# LED_Driver_-_1.net
KiCad netlist of a schematic drawn in Altium Designer
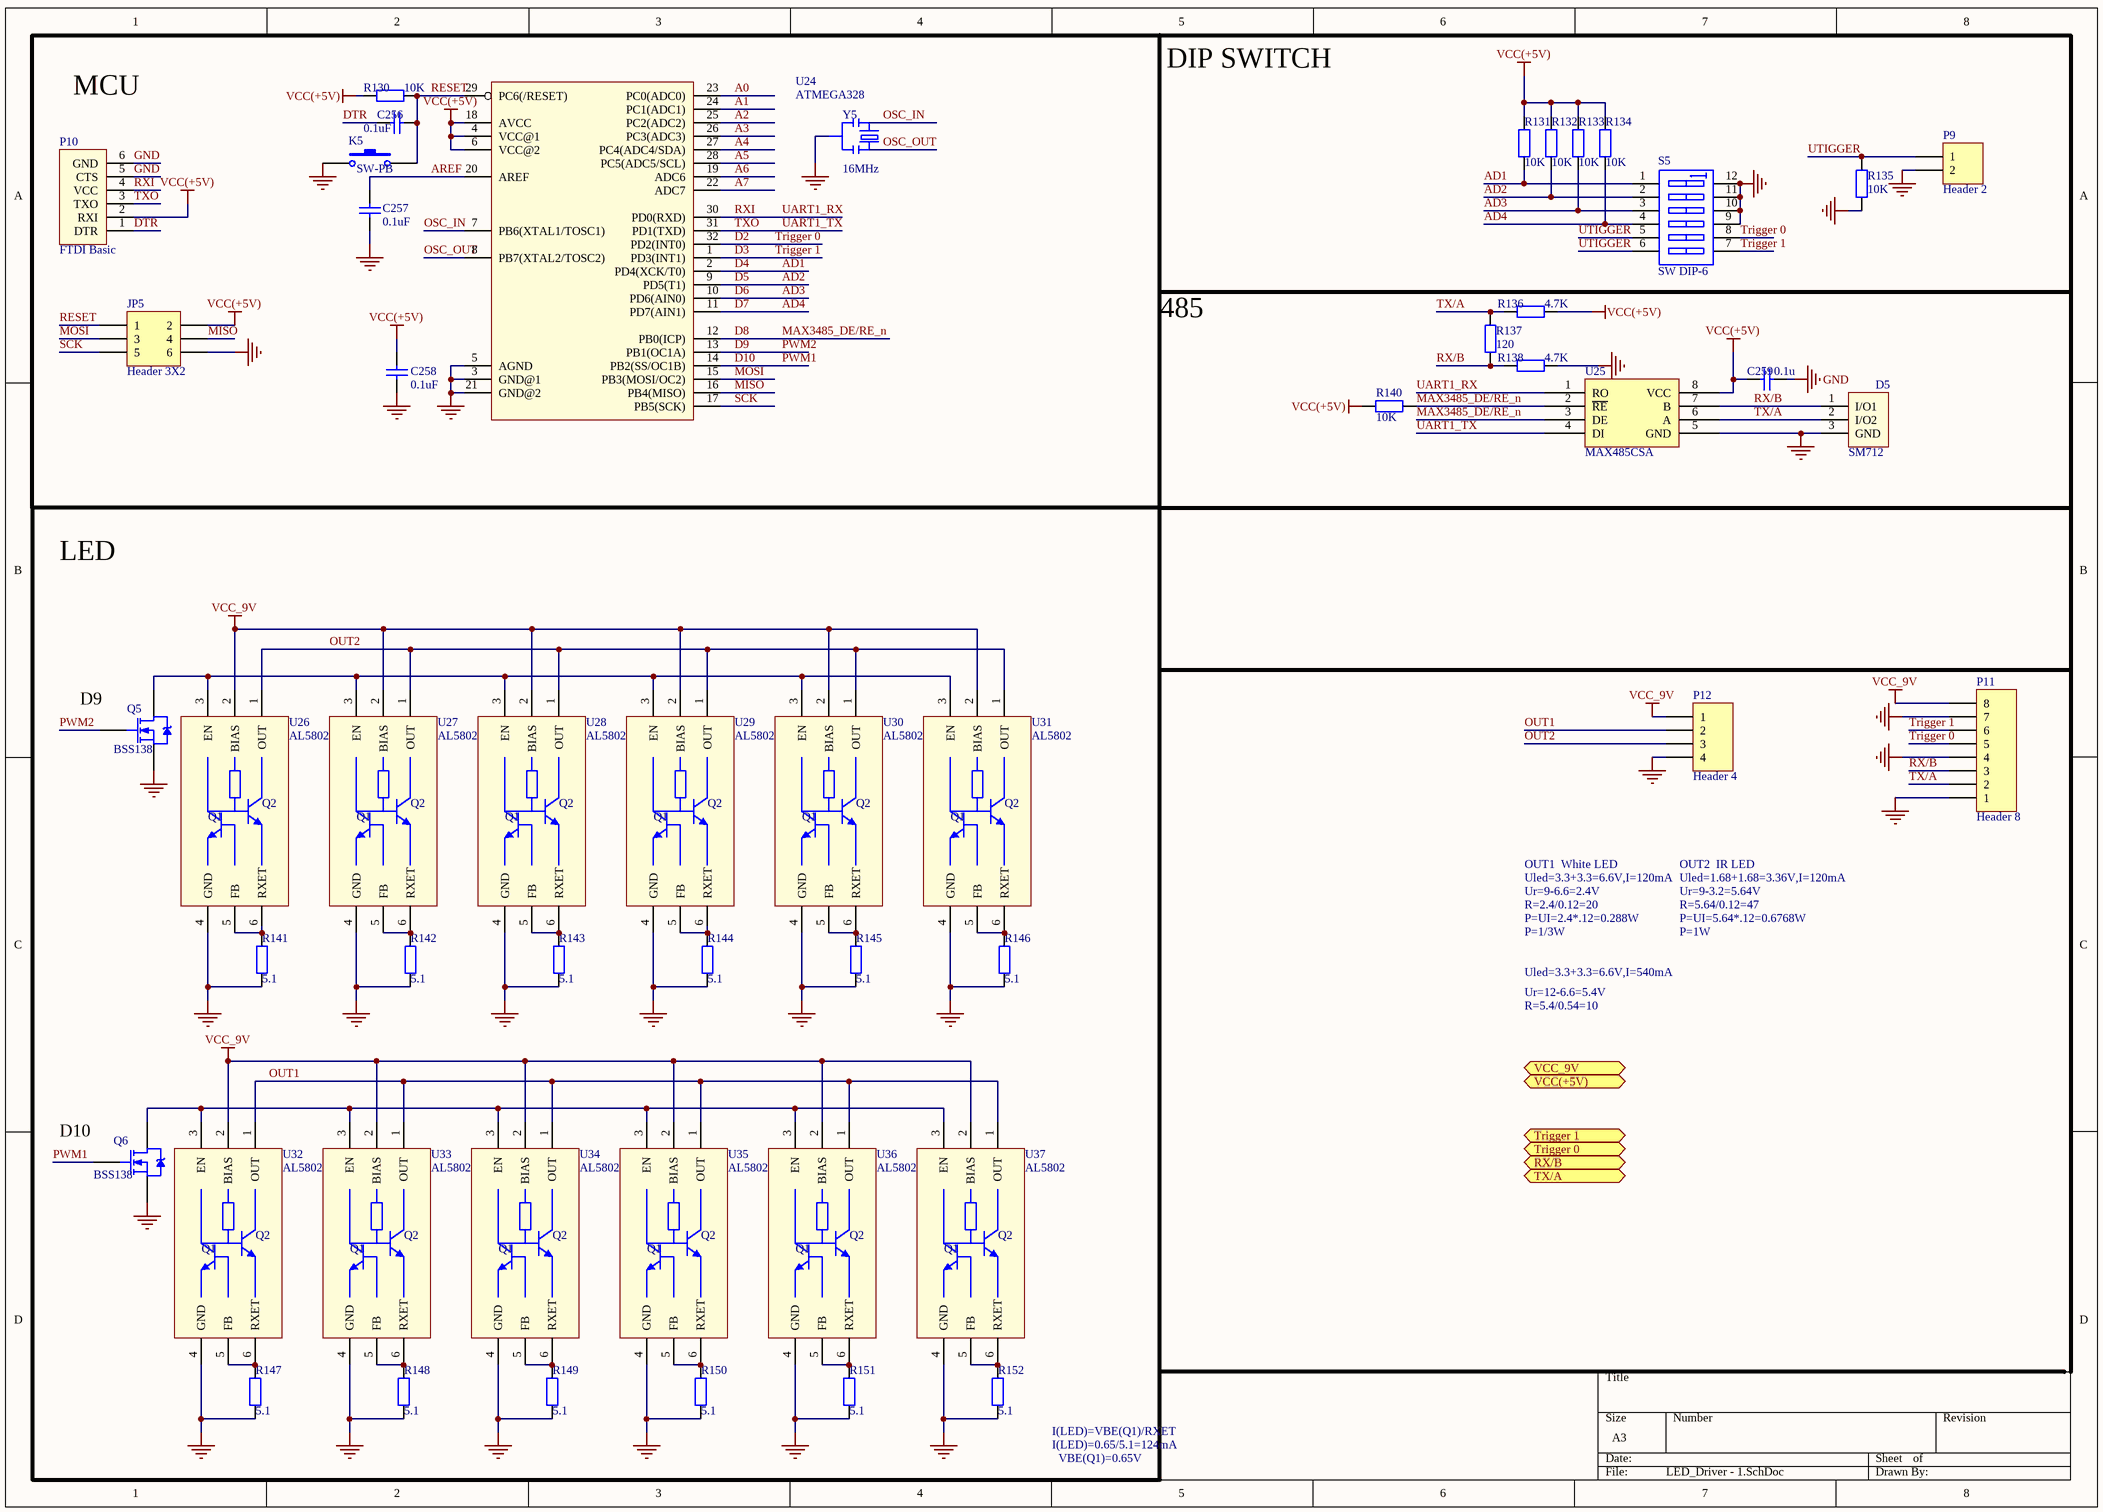
[diagram p0: LED_Driver - 1.SchDoc]

(export (version "E")
  (design (tool "Eeschema 10.0.6"))
  (components
    (comp (ref "C256")
      (value "0.1uF")
      (footprint "C0603")
      (description "Capacitor")
      (fields (field (name "IPARTNUMBER") "C100nF25V10%X7R") (field (name "VOLTAGE") "25V"))
      (libsource (lib "Schlib1") (part "CAP SMT C100nF25V10%X7R"))
    )
    (comp (ref "C257")
      (value "0.1uF")
      (footprint "C0603")
      (description "Capacitor")
      (fields (field (name "IPARTNUMBER") "C100nF25V10%X7R") (field (name "VOLTAGE") "25V"))
      (libsource (lib "Schlib1") (part "CAP SMT C100nF25V10%X7R"))
    )
    (comp (ref "C258")
      (value "0.1uF")
      (footprint "C0603")
      (description "Capacitor")
      (fields (field (name "IPARTNUMBER") "C100nF25V10%X7R") (field (name "VOLTAGE") "25V"))
      (libsource (lib "Schlib1") (part "CAP SMT C100nF25V10%X7R"))
    )
    (comp (ref "C259")
      (value "0.1u")
      (footprint "C0603")
      (description "Capacitor")
      (fields (field (name "PUBLISHER") "Altium Limited"))
      (libsource (lib "Miscellaneous Devices") (part "Cap"))
    )
    (comp (ref "D5")
      (value "SM712")
      (footprint "SOT23-3")
      (libsource (lib "STM32F4_CAM V2.0") (part "SM712"))
    )
    (comp (ref "JP5")
      (value "Header 3X2")
      (footprint "MHDR1X6")
      (description "Header, 3-Pin, Dual row")
      (fields (field (name "PUBLISHER") "Altium Limited"))
      (libsource (lib "Miscellaneous Connectors") (part "Header 3X2"))
    )
    (comp (ref "K5")
      (value "SW-PB")
      (footprint "157SW")
      (description "Switch")
      (fields (field (name "PUBLISHER") "Altium Limited"))
      (libsource (lib "Miscellaneous Devices") (part "SW-PB"))
    )
    (comp (ref "P9")
      (value "Header 2")
      (footprint "HDR1X2")
      (description "Header, 2-Pin")
      (fields (field (name "PUBLISHER") "Altium Limited"))
      (libsource (lib "Miscellaneous Connectors") (part "Header 2"))
    )
    (comp (ref "P10")
      (value "FTDI Basic")
      (footprint "MHDR1X6")
      (libsource (lib "PCB_Project1") (part "ARDUINO_SERIAL_PROGRAMPTH"))
    )
    (comp (ref "P11")
      (value "Header 8")
      (footprint "SH_1.25MM*8")
      (description "Header, 8-Pin")
      (fields (field (name "PUBLISHER") "Altium Limited"))
      (libsource (lib "Miscellaneous Connectors") (part "Header 8"))
    )
    (comp (ref "P12")
      (value "Header 4")
      (footprint "SMT_1.25MM*4")
      (description "Header, 4-Pin")
      (fields (field (name "PUBLISHER") "Altium Limited"))
      (libsource (lib "Miscellaneous Connectors") (part "Header 4"))
    )
    (comp (ref "Q5")
      (value "BSS138")
      (footprint "SOT-23 (Standard)")
      (fields
        (field (name "MANUFACTURER") "Fairchild Semiconductor")
        (field (name "MANUFACTURER PART NUMBER") "BSS123")
      )
      (libsource (lib "Miscellaneous_Devices") (part "NMOS"))
    )
    (comp (ref "Q6")
      (value "BSS138")
      (footprint "SOT-23 (Standard)")
      (fields
        (field (name "MANUFACTURER") "Fairchild Semiconductor")
        (field (name "MANUFACTURER PART NUMBER") "BSS123")
      )
      (libsource (lib "Miscellaneous_Devices") (part "NMOS"))
    )
    (comp (ref "R130")
      (value "10K")
      (footprint "R0603")
      (description "Resistor")
      (libsource (lib "") (part "Res2_2"))
    )
    (comp (ref "R131")
      (value "10K")
      (footprint "R0603")
      (description "Resistor")
      (libsource (lib "DM642") (part "Res2"))
    )
    (comp (ref "R132")
      (value "10K")
      (footprint "R0603")
      (description "Resistor")
      (libsource (lib "DM642") (part "Res2"))
    )
    (comp (ref "R133")
      (value "10K")
      (footprint "R0603")
      (description "Resistor")
      (libsource (lib "DM642") (part "Res2"))
    )
    (comp (ref "R134")
      (value "10K")
      (footprint "R0603")
      (description "Resistor")
      (libsource (lib "DM642") (part "Res2"))
    )
    (comp (ref "R135")
      (value "10K")
      (footprint "R0603")
      (description "Resistor")
      (fields (field (name "PUBLISHER") "Altium Limited"))
      (libsource (lib "Miscellaneous Devices") (part "Res2"))
    )
    (comp (ref "R136")
      (value "4.7K")
      (footprint "R0603")
      (description "Resistor")
      (libsource (lib "") (part "Res2_1"))
    )
    (comp (ref "R137")
      (value "120")
      (footprint "R0603")
      (description "Resistor")
      (libsource (lib "DM642") (part "Res2"))
    )
    (comp (ref "R138")
      (value "4.7K")
      (footprint "R0603")
      (description "Resistor")
      (libsource (lib "") (part "Res2_1"))
    )
    (comp (ref "R140")
      (value "10K")
      (footprint "R0603")
      (description "Resistor")
      (libsource (lib "") (part "Res2_1"))
    )
    (comp (ref "R141")
      (value "5.1")
      (footprint "R0603")
      (description "Resistor")
      (libsource (lib "DM642") (part "Res2"))
    )
    (comp (ref "R142")
      (value "5.1")
      (footprint "R0603")
      (description "Resistor")
      (libsource (lib "DM642") (part "Res2"))
    )
    (comp (ref "R143")
      (value "5.1")
      (footprint "R0603")
      (description "Resistor")
      (libsource (lib "DM642") (part "Res2"))
    )
    (comp (ref "R144")
      (value "5.1")
      (footprint "R0603")
      (description "Resistor")
      (libsource (lib "DM642") (part "Res2"))
    )
    (comp (ref "R145")
      (value "5.1")
      (footprint "R0603")
      (description "Resistor")
      (libsource (lib "DM642") (part "Res2"))
    )
    (comp (ref "R146")
      (value "5.1")
      (footprint "R0603")
      (description "Resistor")
      (libsource (lib "DM642") (part "Res2"))
    )
    (comp (ref "R147")
      (value "5.1")
      (footprint "R0603")
      (description "Resistor")
      (libsource (lib "DM642") (part "Res2"))
    )
    (comp (ref "R148")
      (value "5.1")
      (footprint "R0603")
      (description "Resistor")
      (libsource (lib "DM642") (part "Res2"))
    )
    (comp (ref "R149")
      (value "5.1")
      (footprint "R0603")
      (description "Resistor")
      (libsource (lib "DM642") (part "Res2"))
    )
    (comp (ref "R150")
      (value "5.1")
      (footprint "R0603")
      (description "Resistor")
      (libsource (lib "DM642") (part "Res2"))
    )
    (comp (ref "R151")
      (value "5.1")
      (footprint "R0603")
      (description "Resistor")
      (libsource (lib "DM642") (part "Res2"))
    )
    (comp (ref "R152")
      (value "5.1")
      (footprint "R0603")
      (description "Resistor")
      (libsource (lib "DM642") (part "Res2"))
    )
    (comp (ref "S5")
      (value "SW DIP-6")
      (footprint "DIP_SW_6WAY_SMD")
      (description "DIP Switch, 6 Position, SPST")
      (fields (field (name "PUBLISHER") "Altium Limited"))
      (libsource (lib "Miscellaneous Devices") (part "SW DIP-6"))
    )
    (comp (ref "U24")
      (value "ATMEGA328")
      (footprint "TQFP32-08")
      (libsource (lib "PCB_Project1") (part "ATMEGA168"))
    )
    (comp (ref "U25")
      (value "MAX485CSA")
      (footprint "SOIC-8")
      (libsource (lib "STM32F4_CAM V1.2") (part "MAX3485CSA"))
    )
    (comp (ref "U26") (value "AL5802") (footprint "SOT26") (libsource (lib "LED") (part "AL5802")))
    (comp (ref "U27") (value "AL5802") (footprint "SOT26") (libsource (lib "LED") (part "AL5802")))
    (comp (ref "U28") (value "AL5802") (footprint "SOT26") (libsource (lib "LED") (part "AL5802")))
    (comp (ref "U29") (value "AL5802") (footprint "SOT26") (libsource (lib "LED") (part "AL5802")))
    (comp (ref "U30") (value "AL5802") (footprint "SOT26") (libsource (lib "LED") (part "AL5802")))
    (comp (ref "U31") (value "AL5802") (footprint "SOT26") (libsource (lib "LED") (part "AL5802")))
    (comp (ref "U32") (value "AL5802") (footprint "SOT26") (libsource (lib "LED") (part "AL5802")))
    (comp (ref "U33") (value "AL5802") (footprint "SOT26") (libsource (lib "LED") (part "AL5802")))
    (comp (ref "U34") (value "AL5802") (footprint "SOT26") (libsource (lib "LED") (part "AL5802")))
    (comp (ref "U35") (value "AL5802") (footprint "SOT26") (libsource (lib "LED") (part "AL5802")))
    (comp (ref "U36") (value "AL5802") (footprint "SOT26") (libsource (lib "LED") (part "AL5802")))
    (comp (ref "U37") (value "AL5802") (footprint "SOT26") (libsource (lib "LED") (part "AL5802")))
    (comp (ref "Y5")
      (value "16MHz")
      (footprint "RESONATOR-SMD")
      (libsource (lib "SparkFun") (part "RESONATORSMD"))
    )
  )
  (nets
    (net (code "1") (name "/A0") (class "Default")
      (node (ref "U24") (pin "23") (pinfunction "PC0(ADC0)_23") (pintype "passive"))
    )
    (net (code "2") (name "/A1") (class "Default")
      (node (ref "U24") (pin "24") (pinfunction "PC1(ADC1)_24") (pintype "passive"))
    )
    (net (code "3") (name "/A2") (class "Default")
      (node (ref "U24") (pin "25") (pinfunction "PC2(ADC2)_25") (pintype "passive"))
    )
    (net (code "4") (name "/A3") (class "Default")
      (node (ref "U24") (pin "26") (pinfunction "PC3(ADC3)_26") (pintype "passive"))
    )
    (net (code "5") (name "/A4") (class "Default")
      (node (ref "U24") (pin "27") (pinfunction "PC4(ADC4/SDA)_27") (pintype "passive"))
    )
    (net (code "6") (name "/A5") (class "Default")
      (node (ref "U24") (pin "28") (pinfunction "PC5(ADC5/SCL)_28") (pintype "passive"))
    )
    (net (code "7") (name "/A6") (class "Default")
      (node (ref "U24") (pin "19") (pinfunction "ADC6_19") (pintype "passive"))
    )
    (net (code "8") (name "/A7") (class "Default")
      (node (ref "U24") (pin "22") (pinfunction "ADC7_22") (pintype "passive"))
    )
    (net (code "9") (name "/AD1") (class "Default")
      (node (ref "R131") (pin "2") (pinfunction "2_2") (pintype "passive"))
      (node (ref "S5") (pin "1") (pinfunction "A1_1") (pintype "passive"))
      (node (ref "U24") (pin "2") (pinfunction "PD4(XCK/T0)_2") (pintype "passive"))
    )
    (net (code "10") (name "/AD2") (class "Default")
      (node (ref "R132") (pin "2") (pinfunction "2_2") (pintype "passive"))
      (node (ref "S5") (pin "2") (pinfunction "A2_2") (pintype "passive"))
      (node (ref "U24") (pin "9") (pinfunction "PD5(T1)_9") (pintype "passive"))
    )
    (net (code "11") (name "/AD3") (class "Default")
      (node (ref "R133") (pin "2") (pinfunction "2_2") (pintype "passive"))
      (node (ref "S5") (pin "3") (pinfunction "A3_3") (pintype "passive"))
      (node (ref "U24") (pin "10") (pinfunction "PD6(AIN0)_10") (pintype "passive"))
    )
    (net (code "12") (name "/AD4") (class "Default")
      (node (ref "R134") (pin "2") (pinfunction "2_2") (pintype "passive"))
      (node (ref "S5") (pin "4") (pinfunction "A4_4") (pintype "passive"))
      (node (ref "U24") (pin "11") (pinfunction "PD7(AIN1)_11") (pintype "passive"))
    )
    (net (code "13") (name "/AREF") (class "Default")
      (node (ref "C257") (pin "2") (pinfunction "2_2") (pintype "passive"))
      (node (ref "U24") (pin "20") (pinfunction "AREF_20") (pintype "passive"))
    )
    (net (code "14") (name "/D2") (class "Default")
      (node (ref "P11") (pin "5") (pinfunction "5_5") (pintype "passive"))
      (node (ref "S5") (pin "8") (pinfunction "B5_8") (pintype "passive"))
      (node (ref "U24") (pin "32") (pinfunction "PD2(INT0)_32") (pintype "passive"))
    )
    (net (code "15") (name "/D3") (class "Default")
      (node (ref "P11") (pin "6") (pinfunction "6_6") (pintype "passive"))
      (node (ref "S5") (pin "7") (pinfunction "B6_7") (pintype "passive"))
      (node (ref "U24") (pin "1") (pinfunction "PD3(INT1)_1") (pintype "passive"))
    )
    (net (code "16") (name "/D8") (class "Default")
      (node (ref "R140") (pin "1") (pinfunction "1_1") (pintype "passive"))
      (node (ref "U24") (pin "12") (pinfunction "PB0(ICP)_12") (pintype "passive"))
      (node (ref "U25") (pin "2") (pinfunction "~{RE}_2") (pintype "passive"))
      (node (ref "U25") (pin "3") (pinfunction "DE_3") (pintype "passive"))
    )
    (net (code "17") (name "/D9") (class "Default")
      (node (ref "Q5") (pin "G") (pinfunction "G_G") (pintype "passive"))
      (node (ref "U24") (pin "13") (pinfunction "PB1(OC1A)_13") (pintype "passive"))
    )
    (net (code "18") (name "/D10") (class "Default")
      (node (ref "Q6") (pin "G") (pinfunction "G_G") (pintype "passive"))
      (node (ref "U24") (pin "14") (pinfunction "PB2(SS/OC1B)_14") (pintype "passive"))
    )
    (net (code "19") (name "/DTR") (class "Default")
      (node (ref "C256") (pin "1") (pinfunction "1_1") (pintype "passive"))
      (node (ref "P10") (pin "1") (pinfunction "DTR_1") (pintype "passive"))
    )
    (net (code "20") (name "/MISO") (class "Default")
      (node (ref "JP5") (pin "4") (pinfunction "4_4") (pintype "passive"))
      (node (ref "U24") (pin "16") (pinfunction "PB4(MISO)_16") (pintype "passive"))
    )
    (net (code "21") (name "/MOSI") (class "Default")
      (node (ref "JP5") (pin "3") (pinfunction "3_3") (pintype "passive"))
      (node (ref "U24") (pin "15") (pinfunction "PB3(MOSI/OC2)_15") (pintype "passive"))
    )
    (net (code "22") (name "/OSC_IN") (class "Default")
      (node (ref "U24") (pin "7") (pinfunction "PB6(XTAL1/TOSC1)_7") (pintype "passive"))
      (node (ref "Y5") (pin "3") (pinfunction "3_3") (pintype "passive"))
    )
    (net (code "23") (name "/OSC_OUT") (class "Default")
      (node (ref "U24") (pin "8") (pinfunction "PB7(XTAL2/TOSC2)_8") (pintype "passive"))
      (node (ref "Y5") (pin "1") (pinfunction "1_1") (pintype "passive"))
    )
    (net (code "24") (name "/OUT1") (class "Default")
      (node (ref "P12") (pin "2") (pinfunction "2_2") (pintype "passive"))
      (node (ref "U32") (pin "1") (pinfunction "OUT_1") (pintype "passive"))
      (node (ref "U33") (pin "1") (pinfunction "OUT_1") (pintype "passive"))
      (node (ref "U34") (pin "1") (pinfunction "OUT_1") (pintype "passive"))
      (node (ref "U35") (pin "1") (pinfunction "OUT_1") (pintype "passive"))
      (node (ref "U36") (pin "1") (pinfunction "OUT_1") (pintype "passive"))
      (node (ref "U37") (pin "1") (pinfunction "OUT_1") (pintype "passive"))
    )
    (net (code "25") (name "/OUT2") (class "Default")
      (node (ref "P12") (pin "3") (pinfunction "3_3") (pintype "passive"))
      (node (ref "U26") (pin "1") (pinfunction "OUT_1") (pintype "passive"))
      (node (ref "U27") (pin "1") (pinfunction "OUT_1") (pintype "passive"))
      (node (ref "U28") (pin "1") (pinfunction "OUT_1") (pintype "passive"))
      (node (ref "U29") (pin "1") (pinfunction "OUT_1") (pintype "passive"))
      (node (ref "U30") (pin "1") (pinfunction "OUT_1") (pintype "passive"))
      (node (ref "U31") (pin "1") (pinfunction "OUT_1") (pintype "passive"))
    )
    (net (code "26") (name "/RESET") (class "Default")
      (node (ref "C256") (pin "2") (pinfunction "2_2") (pintype "passive"))
      (node (ref "JP5") (pin "1") (pinfunction "1_1") (pintype "passive"))
      (node (ref "K5") (pin "2") (pinfunction "2_2") (pintype "passive"))
      (node (ref "R130") (pin "2") (pinfunction "2_2") (pintype "passive"))
      (node (ref "U24") (pin "29") (pinfunction "PC6(/RESET)_29") (pintype "passive"))
    )
    (net (code "27") (name "/RXI") (class "Default")
      (node (ref "P10") (pin "4") (pinfunction "VCC_4") (pintype "passive"))
      (node (ref "U24") (pin "30") (pinfunction "PD0(RXD)_30") (pintype "passive"))
      (node (ref "U25") (pin "1") (pinfunction "RO_1") (pintype "passive"))
    )
    (net (code "28") (name "/RX{slash}B") (class "Default")
      (node (ref "D5") (pin "1") (pinfunction "I/O1_1") (pintype "passive"))
      (node (ref "P11") (pin "3") (pinfunction "3_3") (pintype "passive"))
      (node (ref "R137") (pin "2") (pinfunction "2_2") (pintype "passive"))
      (node (ref "R138") (pin "2") (pinfunction "2_2") (pintype "passive"))
      (node (ref "U25") (pin "7") (pinfunction "B_7") (pintype "passive"))
    )
    (net (code "29") (name "/SCK") (class "Default")
      (node (ref "JP5") (pin "5") (pinfunction "5_5") (pintype "passive"))
      (node (ref "U24") (pin "17") (pinfunction "PB5(SCK)_17") (pintype "passive"))
    )
    (net (code "30") (name "/TXO") (class "Default")
      (node (ref "P10") (pin "3") (pinfunction "TXO_3") (pintype "passive"))
      (node (ref "U24") (pin "31") (pinfunction "PD1(TXD)_31") (pintype "passive"))
      (node (ref "U25") (pin "4") (pinfunction "DI_4") (pintype "passive"))
    )
    (net (code "31") (name "/TX{slash}A") (class "Default")
      (node (ref "D5") (pin "2") (pinfunction "I/O2_2") (pintype "passive"))
      (node (ref "P11") (pin "2") (pinfunction "2_2") (pintype "passive"))
      (node (ref "R136") (pin "2") (pinfunction "2_2") (pintype "passive"))
      (node (ref "R137") (pin "1") (pinfunction "1_1") (pintype "passive"))
      (node (ref "U25") (pin "6") (pinfunction "A_6") (pintype "passive"))
    )
    (net (code "32") (name "/UTIGGER") (class "Default")
      (node (ref "P9") (pin "1") (pinfunction "1_1") (pintype "passive"))
      (node (ref "R135") (pin "2") (pinfunction "2_2") (pintype "passive"))
      (node (ref "S5") (pin "5") (pinfunction "A5_5") (pintype "passive"))
      (node (ref "S5") (pin "6") (pinfunction "A6_6") (pintype "passive"))
    )
    (net (code "33") (name "GND") (class "Default")
      (node (ref "C257") (pin "1") (pinfunction "1_1") (pintype "passive"))
      (node (ref "C258") (pin "2") (pinfunction "2_2") (pintype "passive"))
      (node (ref "C259") (pin "1") (pinfunction "1_1") (pintype "passive"))
      (node (ref "D5") (pin "3") (pinfunction "GND_3") (pintype "passive"))
      (node (ref "JP5") (pin "6") (pinfunction "6_6") (pintype "passive"))
      (node (ref "K5") (pin "1") (pinfunction "1_1") (pintype "passive"))
      (node (ref "P10") (pin "5") (pinfunction "CTS_5") (pintype "passive"))
      (node (ref "P10") (pin "6") (pinfunction "GND_6") (pintype "passive"))
      (node (ref "P11") (pin "1") (pinfunction "1_1") (pintype "passive"))
      (node (ref "P11") (pin "4") (pinfunction "4_4") (pintype "passive"))
      (node (ref "P11") (pin "7") (pinfunction "7_7") (pintype "passive"))
      (node (ref "P12") (pin "4") (pinfunction "4_4") (pintype "passive"))
      (node (ref "P9") (pin "2") (pinfunction "2_2") (pintype "passive"))
      (node (ref "Q5") (pin "S") (pinfunction "S_S") (pintype "passive"))
      (node (ref "Q6") (pin "S") (pinfunction "S_S") (pintype "passive"))
      (node (ref "R135") (pin "1") (pinfunction "1_1") (pintype "passive"))
      (node (ref "R138") (pin "1") (pinfunction "1_1") (pintype "passive"))
      (node (ref "R141") (pin "2") (pinfunction "2_2") (pintype "passive"))
      (node (ref "R142") (pin "2") (pinfunction "2_2") (pintype "passive"))
      (node (ref "R143") (pin "2") (pinfunction "2_2") (pintype "passive"))
      (node (ref "R144") (pin "2") (pinfunction "2_2") (pintype "passive"))
      (node (ref "R145") (pin "2") (pinfunction "2_2") (pintype "passive"))
      (node (ref "R146") (pin "2") (pinfunction "2_2") (pintype "passive"))
      (node (ref "R147") (pin "2") (pinfunction "2_2") (pintype "passive"))
      (node (ref "R148") (pin "2") (pinfunction "2_2") (pintype "passive"))
      (node (ref "R149") (pin "2") (pinfunction "2_2") (pintype "passive"))
      (node (ref "R150") (pin "2") (pinfunction "2_2") (pintype "passive"))
      (node (ref "R151") (pin "2") (pinfunction "2_2") (pintype "passive"))
      (node (ref "R152") (pin "2") (pinfunction "2_2") (pintype "passive"))
      (node (ref "S5") (pin "10") (pinfunction "B3_10") (pintype "passive"))
      (node (ref "S5") (pin "11") (pinfunction "B2_11") (pintype "passive"))
      (node (ref "S5") (pin "12") (pinfunction "B1_12") (pintype "passive"))
      (node (ref "S5") (pin "9") (pinfunction "B4_9") (pintype "passive"))
      (node (ref "U24") (pin "21") (pinfunction "GND@2_21") (pintype "passive"))
      (node (ref "U24") (pin "3") (pinfunction "GND@1_3") (pintype "passive"))
      (node (ref "U24") (pin "5") (pinfunction "AGND_5") (pintype "passive"))
      (node (ref "U25") (pin "5") (pinfunction "GND_5") (pintype "passive"))
      (node (ref "U26") (pin "4") (pinfunction "GND_4") (pintype "passive"))
      (node (ref "U27") (pin "4") (pinfunction "GND_4") (pintype "passive"))
      (node (ref "U28") (pin "4") (pinfunction "GND_4") (pintype "passive"))
      (node (ref "U29") (pin "4") (pinfunction "GND_4") (pintype "passive"))
      (node (ref "U30") (pin "4") (pinfunction "GND_4") (pintype "passive"))
      (node (ref "U31") (pin "4") (pinfunction "GND_4") (pintype "passive"))
      (node (ref "U32") (pin "4") (pinfunction "GND_4") (pintype "passive"))
      (node (ref "U33") (pin "4") (pinfunction "GND_4") (pintype "passive"))
      (node (ref "U34") (pin "4") (pinfunction "GND_4") (pintype "passive"))
      (node (ref "U35") (pin "4") (pinfunction "GND_4") (pintype "passive"))
      (node (ref "U36") (pin "4") (pinfunction "GND_4") (pintype "passive"))
      (node (ref "U37") (pin "4") (pinfunction "GND_4") (pintype "passive"))
      (node (ref "Y5") (pin "2") (pinfunction "2_2") (pintype "passive"))
    )
    (net (code "34") (name "Net-(U26-EN)") (class "Default")
      (node (ref "Q5") (pin "D") (pinfunction "D_D") (pintype "passive"))
      (node (ref "U26") (pin "3") (pinfunction "EN_3") (pintype "passive"))
      (node (ref "U27") (pin "3") (pinfunction "EN_3") (pintype "passive"))
      (node (ref "U28") (pin "3") (pinfunction "EN_3") (pintype "passive"))
      (node (ref "U29") (pin "3") (pinfunction "EN_3") (pintype "passive"))
      (node (ref "U30") (pin "3") (pinfunction "EN_3") (pintype "passive"))
      (node (ref "U31") (pin "3") (pinfunction "EN_3") (pintype "passive"))
    )
    (net (code "35") (name "Net-(U26-FB)") (class "Default")
      (node (ref "R141") (pin "1") (pinfunction "1_1") (pintype "passive"))
      (node (ref "U26") (pin "5") (pinfunction "FB_5") (pintype "passive"))
      (node (ref "U26") (pin "6") (pinfunction "RXET_6") (pintype "passive"))
    )
    (net (code "36") (name "Net-(U27-FB)") (class "Default")
      (node (ref "R142") (pin "1") (pinfunction "1_1") (pintype "passive"))
      (node (ref "U27") (pin "5") (pinfunction "FB_5") (pintype "passive"))
      (node (ref "U27") (pin "6") (pinfunction "RXET_6") (pintype "passive"))
    )
    (net (code "37") (name "Net-(U28-FB)") (class "Default")
      (node (ref "R143") (pin "1") (pinfunction "1_1") (pintype "passive"))
      (node (ref "U28") (pin "5") (pinfunction "FB_5") (pintype "passive"))
      (node (ref "U28") (pin "6") (pinfunction "RXET_6") (pintype "passive"))
    )
    (net (code "38") (name "Net-(U29-FB)") (class "Default")
      (node (ref "R144") (pin "1") (pinfunction "1_1") (pintype "passive"))
      (node (ref "U29") (pin "5") (pinfunction "FB_5") (pintype "passive"))
      (node (ref "U29") (pin "6") (pinfunction "RXET_6") (pintype "passive"))
    )
    (net (code "39") (name "Net-(U30-FB)") (class "Default")
      (node (ref "R145") (pin "1") (pinfunction "1_1") (pintype "passive"))
      (node (ref "U30") (pin "5") (pinfunction "FB_5") (pintype "passive"))
      (node (ref "U30") (pin "6") (pinfunction "RXET_6") (pintype "passive"))
    )
    (net (code "40") (name "Net-(U31-FB)") (class "Default")
      (node (ref "R146") (pin "1") (pinfunction "1_1") (pintype "passive"))
      (node (ref "U31") (pin "5") (pinfunction "FB_5") (pintype "passive"))
      (node (ref "U31") (pin "6") (pinfunction "RXET_6") (pintype "passive"))
    )
    (net (code "41") (name "Net-(U32-EN)") (class "Default")
      (node (ref "Q6") (pin "D") (pinfunction "D_D") (pintype "passive"))
      (node (ref "U32") (pin "3") (pinfunction "EN_3") (pintype "passive"))
      (node (ref "U33") (pin "3") (pinfunction "EN_3") (pintype "passive"))
      (node (ref "U34") (pin "3") (pinfunction "EN_3") (pintype "passive"))
      (node (ref "U35") (pin "3") (pinfunction "EN_3") (pintype "passive"))
      (node (ref "U36") (pin "3") (pinfunction "EN_3") (pintype "passive"))
      (node (ref "U37") (pin "3") (pinfunction "EN_3") (pintype "passive"))
    )
    (net (code "42") (name "Net-(U32-FB)") (class "Default")
      (node (ref "R147") (pin "1") (pinfunction "1_1") (pintype "passive"))
      (node (ref "U32") (pin "5") (pinfunction "FB_5") (pintype "passive"))
      (node (ref "U32") (pin "6") (pinfunction "RXET_6") (pintype "passive"))
    )
    (net (code "43") (name "Net-(U33-FB)") (class "Default")
      (node (ref "R148") (pin "1") (pinfunction "1_1") (pintype "passive"))
      (node (ref "U33") (pin "5") (pinfunction "FB_5") (pintype "passive"))
      (node (ref "U33") (pin "6") (pinfunction "RXET_6") (pintype "passive"))
    )
    (net (code "44") (name "Net-(U34-FB)") (class "Default")
      (node (ref "R149") (pin "1") (pinfunction "1_1") (pintype "passive"))
      (node (ref "U34") (pin "5") (pinfunction "FB_5") (pintype "passive"))
      (node (ref "U34") (pin "6") (pinfunction "RXET_6") (pintype "passive"))
    )
    (net (code "45") (name "Net-(U35-FB)") (class "Default")
      (node (ref "R150") (pin "1") (pinfunction "1_1") (pintype "passive"))
      (node (ref "U35") (pin "5") (pinfunction "FB_5") (pintype "passive"))
      (node (ref "U35") (pin "6") (pinfunction "RXET_6") (pintype "passive"))
    )
    (net (code "46") (name "Net-(U36-FB)") (class "Default")
      (node (ref "R151") (pin "1") (pinfunction "1_1") (pintype "passive"))
      (node (ref "U36") (pin "5") (pinfunction "FB_5") (pintype "passive"))
      (node (ref "U36") (pin "6") (pinfunction "RXET_6") (pintype "passive"))
    )
    (net (code "47") (name "Net-(U37-FB)") (class "Default")
      (node (ref "R152") (pin "1") (pinfunction "1_1") (pintype "passive"))
      (node (ref "U37") (pin "5") (pinfunction "FB_5") (pintype "passive"))
      (node (ref "U37") (pin "6") (pinfunction "RXET_6") (pintype "passive"))
    )
    (net (code "48") (name "VCC(+5V)") (class "Default")
      (node (ref "C258") (pin "1") (pinfunction "1_1") (pintype "passive"))
      (node (ref "C259") (pin "2") (pinfunction "2_2") (pintype "passive"))
      (node (ref "JP5") (pin "2") (pinfunction "2_2") (pintype "passive"))
      (node (ref "P10") (pin "2") (pinfunction "RXI_2") (pintype "passive"))
      (node (ref "R130") (pin "1") (pinfunction "1_1") (pintype "passive"))
      (node (ref "R131") (pin "1") (pinfunction "1_1") (pintype "passive"))
      (node (ref "R132") (pin "1") (pinfunction "1_1") (pintype "passive"))
      (node (ref "R133") (pin "1") (pinfunction "1_1") (pintype "passive"))
      (node (ref "R134") (pin "1") (pinfunction "1_1") (pintype "passive"))
      (node (ref "R136") (pin "1") (pinfunction "1_1") (pintype "passive"))
      (node (ref "R140") (pin "2") (pinfunction "2_2") (pintype "passive"))
      (node (ref "U24") (pin "18") (pinfunction "AVCC_18") (pintype "passive"))
      (node (ref "U24") (pin "4") (pinfunction "VCC@1_4") (pintype "passive"))
      (node (ref "U24") (pin "6") (pinfunction "VCC@2_6") (pintype "passive"))
      (node (ref "U25") (pin "8") (pinfunction "VCC_8") (pintype "passive"))
    )
    (net (code "49") (name "VCC_9V") (class "Default")
      (node (ref "P11") (pin "8") (pinfunction "8_8") (pintype "passive"))
      (node (ref "P12") (pin "1") (pinfunction "1_1") (pintype "passive"))
      (node (ref "U26") (pin "2") (pinfunction "BIAS_2") (pintype "passive"))
      (node (ref "U27") (pin "2") (pinfunction "BIAS_2") (pintype "passive"))
      (node (ref "U28") (pin "2") (pinfunction "BIAS_2") (pintype "passive"))
      (node (ref "U29") (pin "2") (pinfunction "BIAS_2") (pintype "passive"))
      (node (ref "U30") (pin "2") (pinfunction "BIAS_2") (pintype "passive"))
      (node (ref "U31") (pin "2") (pinfunction "BIAS_2") (pintype "passive"))
      (node (ref "U32") (pin "2") (pinfunction "BIAS_2") (pintype "passive"))
      (node (ref "U33") (pin "2") (pinfunction "BIAS_2") (pintype "passive"))
      (node (ref "U34") (pin "2") (pinfunction "BIAS_2") (pintype "passive"))
      (node (ref "U35") (pin "2") (pinfunction "BIAS_2") (pintype "passive"))
      (node (ref "U36") (pin "2") (pinfunction "BIAS_2") (pintype "passive"))
      (node (ref "U37") (pin "2") (pinfunction "BIAS_2") (pintype "passive"))
    )
  )
)
